# 1-sch.net
KiCad netlist of a schematic drawn in Altium Designer
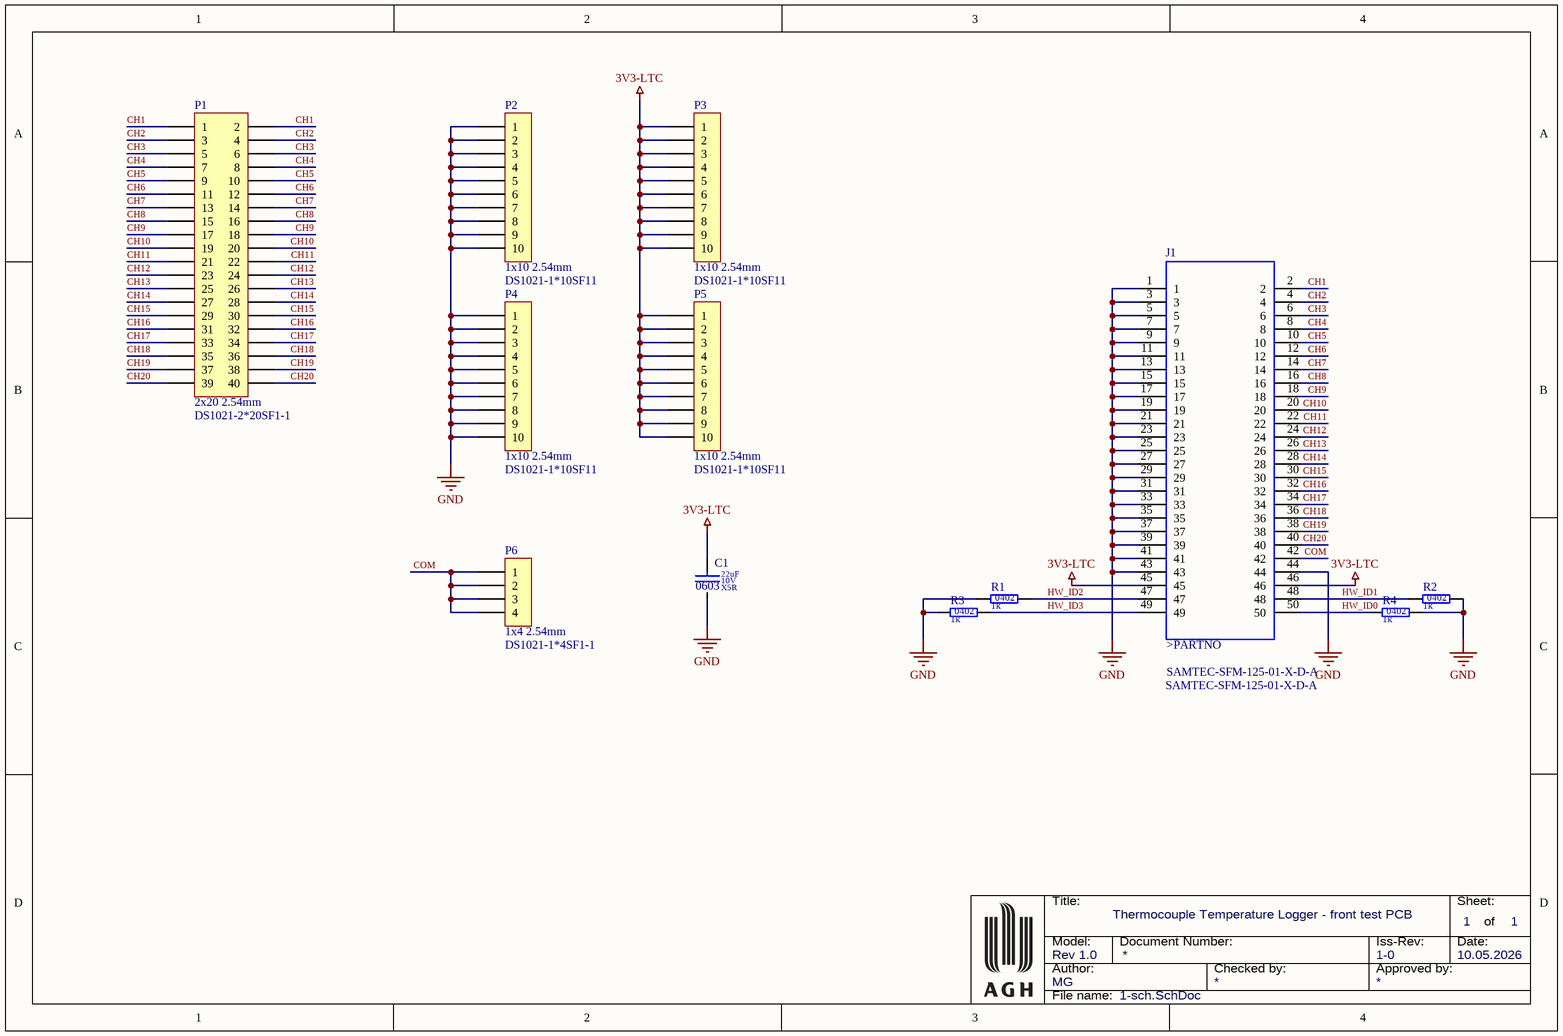
[diagram p0: 1-sch.SchDoc]

(export (version "E")
  (design (tool "Eeschema 10.0.6"))
  (components
    (comp (ref "C1")
      (value "22uF")
      (footprint "C_0603_1608")
      (description "Capacitor")
      (fields
        (field (name "DIELECTRIC") "X5R")
        (field (name "VOLTAGE") "10V")
        (field (name "SCH_FOOTPRINT") "0603")
        (field (name "PART NUMBER") "C_22uF_10V_X5R_0603_20")
        (field (name "MANUFACTURER") "Murata")
      )
      (libsource (lib "Library") (part "C"))
    )
    (comp (ref "J1")
      (value "SAMTEC-SFM-125-01-X-D-A")
      (footprint "SAMTEC-SFM-125-01-X-D-A")
      (libsource (lib "SAMTEC-SFM-125-01-X-D-A") (part "SAMTEC-SFM-125-01-X-D-A"))
    )
    (comp (ref "P1")
      (value "DS1021-2*20SF1-1")
      (footprint "P_HEADER_2x20_2.54")
      (description "Pin Header")
      (fields
        (field (name "SCH_FOOTPRINT") "2x20 2.54mm")
        (field (name "PART NUMBER") "P_HEADER_2x20_2.54")
        (field (name "MANUFACTURER") "Connfly")
      )
      (libsource (lib "Library") (part "P_HEADER_2x20"))
    )
    (comp (ref "P2")
      (value "DS1021-1*10SF11")
      (footprint "P_HEADER_1x10_2.54")
      (description "Pin Header")
      (fields
        (field (name "SCH_FOOTPRINT") "1x10 2.54mm")
        (field (name "PART NUMBER") "P_HEADER_1x10_2.54")
        (field (name "MANUFACTURER") "Connfly")
      )
      (libsource (lib "Library") (part "P_HEADER_1x10"))
    )
    (comp (ref "P3")
      (value "DS1021-1*10SF11")
      (footprint "P_HEADER_1x10_2.54")
      (description "Pin Header")
      (fields
        (field (name "SCH_FOOTPRINT") "1x10 2.54mm")
        (field (name "PART NUMBER") "P_HEADER_1x10_2.54")
        (field (name "MANUFACTURER") "Connfly")
      )
      (libsource (lib "Library") (part "P_HEADER_1x10"))
    )
    (comp (ref "P4")
      (value "DS1021-1*10SF11")
      (footprint "P_HEADER_1x10_2.54")
      (description "Pin Header")
      (fields
        (field (name "SCH_FOOTPRINT") "1x10 2.54mm")
        (field (name "PART NUMBER") "P_HEADER_1x10_2.54")
        (field (name "MANUFACTURER") "Connfly")
      )
      (libsource (lib "Library") (part "P_HEADER_1x10"))
    )
    (comp (ref "P5")
      (value "DS1021-1*10SF11")
      (footprint "P_HEADER_1x10_2.54")
      (description "Pin Header")
      (fields
        (field (name "SCH_FOOTPRINT") "1x10 2.54mm")
        (field (name "PART NUMBER") "P_HEADER_1x10_2.54")
        (field (name "MANUFACTURER") "Connfly")
      )
      (libsource (lib "Library") (part "P_HEADER_1x10"))
    )
    (comp (ref "P6")
      (value "DS1021-1*4SF1-1")
      (footprint "P_HEADER_1x4_2.54")
      (description "Pin Header")
      (fields
        (field (name "SCH_FOOTPRINT") "1x4 2.54mm")
        (field (name "PART NUMBER") "P_HEADER_1x4_2.54")
        (field (name "MANUFACTURER") "Connfly")
      )
      (libsource (lib "Library") (part "P_HEADER_1x4"))
    )
    (comp (ref "R1")
      (value "1k")
      (footprint "R_0402_1005")
      (fields
        (field (name "SCH_FOOTPRINT") "0402")
        (field (name "PART NUMBER") "R_1k_0402_1")
        (field (name "VOLTAGE") "50V")
        (field (name "POWER") "63mW")
      )
      (libsource (lib "Library") (part "R"))
    )
    (comp (ref "R2")
      (value "1k")
      (footprint "R_0402_1005")
      (fields
        (field (name "SCH_FOOTPRINT") "0402")
        (field (name "PART NUMBER") "R_1k_0402_1")
        (field (name "VOLTAGE") "50V")
        (field (name "POWER") "63mW")
      )
      (libsource (lib "Library") (part "R"))
    )
    (comp (ref "R3")
      (value "1k")
      (footprint "R_0402_1005")
      (fields
        (field (name "SCH_FOOTPRINT") "0402")
        (field (name "PART NUMBER") "R_1k_0402_1")
        (field (name "VOLTAGE") "50V")
        (field (name "POWER") "63mW")
      )
      (libsource (lib "Library") (part "R"))
    )
    (comp (ref "R4")
      (value "1k")
      (footprint "R_0402_1005")
      (fields
        (field (name "SCH_FOOTPRINT") "0402")
        (field (name "PART NUMBER") "R_1k_0402_1")
        (field (name "VOLTAGE") "50V")
        (field (name "POWER") "63mW")
      )
      (libsource (lib "Library") (part "R"))
    )
  )
  (nets
    (net (code "1") (name "/CH1") (class "Default")
      (node (ref "J1") (pin "2") (pinfunction "2_2") (pintype "passive"))
      (node (ref "P1") (pin "1") (pinfunction "1_1") (pintype "passive"))
      (node (ref "P1") (pin "2") (pinfunction "2_2") (pintype "passive"))
    )
    (net (code "2") (name "/CH2") (class "Default")
      (node (ref "J1") (pin "4") (pinfunction "4_4") (pintype "passive"))
      (node (ref "P1") (pin "3") (pinfunction "3_3") (pintype "passive"))
      (node (ref "P1") (pin "4") (pinfunction "4_4") (pintype "passive"))
    )
    (net (code "3") (name "/CH3") (class "Default")
      (node (ref "J1") (pin "6") (pinfunction "6_6") (pintype "passive"))
      (node (ref "P1") (pin "5") (pinfunction "5_5") (pintype "passive"))
      (node (ref "P1") (pin "6") (pinfunction "6_6") (pintype "passive"))
    )
    (net (code "4") (name "/CH4") (class "Default")
      (node (ref "J1") (pin "8") (pinfunction "8_8") (pintype "passive"))
      (node (ref "P1") (pin "7") (pinfunction "7_7") (pintype "passive"))
      (node (ref "P1") (pin "8") (pinfunction "8_8") (pintype "passive"))
    )
    (net (code "5") (name "/CH5") (class "Default")
      (node (ref "J1") (pin "10") (pinfunction "10_10") (pintype "passive"))
      (node (ref "P1") (pin "10") (pinfunction "10_10") (pintype "passive"))
      (node (ref "P1") (pin "9") (pinfunction "9_9") (pintype "passive"))
    )
    (net (code "6") (name "/CH6") (class "Default")
      (node (ref "J1") (pin "12") (pinfunction "12_12") (pintype "passive"))
      (node (ref "P1") (pin "11") (pinfunction "11_11") (pintype "passive"))
      (node (ref "P1") (pin "12") (pinfunction "12_12") (pintype "passive"))
    )
    (net (code "7") (name "/CH7") (class "Default")
      (node (ref "J1") (pin "14") (pinfunction "14_14") (pintype "passive"))
      (node (ref "P1") (pin "13") (pinfunction "13_13") (pintype "passive"))
      (node (ref "P1") (pin "14") (pinfunction "14_14") (pintype "passive"))
    )
    (net (code "8") (name "/CH8") (class "Default")
      (node (ref "J1") (pin "16") (pinfunction "16_16") (pintype "passive"))
      (node (ref "P1") (pin "15") (pinfunction "15_15") (pintype "passive"))
      (node (ref "P1") (pin "16") (pinfunction "16_16") (pintype "passive"))
    )
    (net (code "9") (name "/CH9") (class "Default")
      (node (ref "J1") (pin "18") (pinfunction "18_18") (pintype "passive"))
      (node (ref "P1") (pin "17") (pinfunction "17_17") (pintype "passive"))
      (node (ref "P1") (pin "18") (pinfunction "18_18") (pintype "passive"))
    )
    (net (code "10") (name "/CH10") (class "Default")
      (node (ref "J1") (pin "20") (pinfunction "20_20") (pintype "passive"))
      (node (ref "P1") (pin "19") (pinfunction "19_19") (pintype "passive"))
      (node (ref "P1") (pin "20") (pinfunction "20_20") (pintype "passive"))
    )
    (net (code "11") (name "/CH11") (class "Default")
      (node (ref "J1") (pin "22") (pinfunction "22_22") (pintype "passive"))
      (node (ref "P1") (pin "21") (pinfunction "21_21") (pintype "passive"))
      (node (ref "P1") (pin "22") (pinfunction "22_22") (pintype "passive"))
    )
    (net (code "12") (name "/CH12") (class "Default")
      (node (ref "J1") (pin "24") (pinfunction "24_24") (pintype "passive"))
      (node (ref "P1") (pin "23") (pinfunction "23_23") (pintype "passive"))
      (node (ref "P1") (pin "24") (pinfunction "24_24") (pintype "passive"))
    )
    (net (code "13") (name "/CH13") (class "Default")
      (node (ref "J1") (pin "26") (pinfunction "26_26") (pintype "passive"))
      (node (ref "P1") (pin "25") (pinfunction "25_25") (pintype "passive"))
      (node (ref "P1") (pin "26") (pinfunction "26_26") (pintype "passive"))
    )
    (net (code "14") (name "/CH14") (class "Default")
      (node (ref "J1") (pin "28") (pinfunction "28_28") (pintype "passive"))
      (node (ref "P1") (pin "27") (pinfunction "27_27") (pintype "passive"))
      (node (ref "P1") (pin "28") (pinfunction "28_28") (pintype "passive"))
    )
    (net (code "15") (name "/CH15") (class "Default")
      (node (ref "J1") (pin "30") (pinfunction "30_30") (pintype "passive"))
      (node (ref "P1") (pin "29") (pinfunction "29_29") (pintype "passive"))
      (node (ref "P1") (pin "30") (pinfunction "30_30") (pintype "passive"))
    )
    (net (code "16") (name "/CH16") (class "Default")
      (node (ref "J1") (pin "32") (pinfunction "32_32") (pintype "passive"))
      (node (ref "P1") (pin "31") (pinfunction "31_31") (pintype "passive"))
      (node (ref "P1") (pin "32") (pinfunction "32_32") (pintype "passive"))
    )
    (net (code "17") (name "/CH17") (class "Default")
      (node (ref "J1") (pin "34") (pinfunction "34_34") (pintype "passive"))
      (node (ref "P1") (pin "33") (pinfunction "33_33") (pintype "passive"))
      (node (ref "P1") (pin "34") (pinfunction "34_34") (pintype "passive"))
    )
    (net (code "18") (name "/CH18") (class "Default")
      (node (ref "J1") (pin "36") (pinfunction "36_36") (pintype "passive"))
      (node (ref "P1") (pin "35") (pinfunction "35_35") (pintype "passive"))
      (node (ref "P1") (pin "36") (pinfunction "36_36") (pintype "passive"))
    )
    (net (code "19") (name "/CH19") (class "Default")
      (node (ref "J1") (pin "38") (pinfunction "38_38") (pintype "passive"))
      (node (ref "P1") (pin "37") (pinfunction "37_37") (pintype "passive"))
      (node (ref "P1") (pin "38") (pinfunction "38_38") (pintype "passive"))
    )
    (net (code "20") (name "/CH20") (class "Default")
      (node (ref "J1") (pin "40") (pinfunction "40_40") (pintype "passive"))
      (node (ref "P1") (pin "39") (pinfunction "39_39") (pintype "passive"))
      (node (ref "P1") (pin "40") (pinfunction "40_40") (pintype "passive"))
    )
    (net (code "21") (name "/COM") (class "Default")
      (node (ref "J1") (pin "42") (pinfunction "42_42") (pintype "passive"))
      (node (ref "P6") (pin "1") (pinfunction "1_1") (pintype "passive"))
      (node (ref "P6") (pin "2") (pinfunction "2_2") (pintype "passive"))
      (node (ref "P6") (pin "3") (pinfunction "3_3") (pintype "passive"))
      (node (ref "P6") (pin "4") (pinfunction "4_4") (pintype "passive"))
    )
    (net (code "22") (name "/HW_ID0") (class "Default")
      (node (ref "J1") (pin "50") (pinfunction "50_50") (pintype "passive"))
      (node (ref "R4") (pin "1") (pinfunction "1_1") (pintype "passive"))
    )
    (net (code "23") (name "/HW_ID1") (class "Default")
      (node (ref "J1") (pin "48") (pinfunction "48_48") (pintype "passive"))
      (node (ref "R2") (pin "1") (pinfunction "1_1") (pintype "passive"))
    )
    (net (code "24") (name "/HW_ID2") (class "Default")
      (node (ref "J1") (pin "47") (pinfunction "47_47") (pintype "passive"))
      (node (ref "R1") (pin "2") (pinfunction "2_2") (pintype "passive"))
    )
    (net (code "25") (name "/HW_ID3") (class "Default")
      (node (ref "J1") (pin "49") (pinfunction "49_49") (pintype "passive"))
      (node (ref "R3") (pin "2") (pinfunction "2_2") (pintype "passive"))
    )
    (net (code "26") (name "3V3-LTC") (class "Default")
      (node (ref "C1") (pin "1") (pinfunction "1_1") (pintype "passive"))
      (node (ref "J1") (pin "45") (pinfunction "45_45") (pintype "passive"))
      (node (ref "J1") (pin "46") (pinfunction "46_46") (pintype "passive"))
      (node (ref "P3") (pin "1") (pinfunction "1_1") (pintype "passive"))
      (node (ref "P3") (pin "10") (pinfunction "10_10") (pintype "passive"))
      (node (ref "P3") (pin "2") (pinfunction "2_2") (pintype "passive"))
      (node (ref "P3") (pin "3") (pinfunction "3_3") (pintype "passive"))
      (node (ref "P3") (pin "4") (pinfunction "4_4") (pintype "passive"))
      (node (ref "P3") (pin "5") (pinfunction "5_5") (pintype "passive"))
      (node (ref "P3") (pin "6") (pinfunction "6_6") (pintype "passive"))
      (node (ref "P3") (pin "7") (pinfunction "7_7") (pintype "passive"))
      (node (ref "P3") (pin "8") (pinfunction "8_8") (pintype "passive"))
      (node (ref "P3") (pin "9") (pinfunction "9_9") (pintype "passive"))
      (node (ref "P5") (pin "1") (pinfunction "1_1") (pintype "passive"))
      (node (ref "P5") (pin "10") (pinfunction "10_10") (pintype "passive"))
      (node (ref "P5") (pin "2") (pinfunction "2_2") (pintype "passive"))
      (node (ref "P5") (pin "3") (pinfunction "3_3") (pintype "passive"))
      (node (ref "P5") (pin "4") (pinfunction "4_4") (pintype "passive"))
      (node (ref "P5") (pin "5") (pinfunction "5_5") (pintype "passive"))
      (node (ref "P5") (pin "6") (pinfunction "6_6") (pintype "passive"))
      (node (ref "P5") (pin "7") (pinfunction "7_7") (pintype "passive"))
      (node (ref "P5") (pin "8") (pinfunction "8_8") (pintype "passive"))
      (node (ref "P5") (pin "9") (pinfunction "9_9") (pintype "passive"))
    )
    (net (code "27") (name "GND") (class "Default")
      (node (ref "C1") (pin "2") (pinfunction "2_2") (pintype "passive"))
      (node (ref "J1") (pin "1") (pinfunction "1_1") (pintype "passive"))
      (node (ref "J1") (pin "11") (pinfunction "11_11") (pintype "passive"))
      (node (ref "J1") (pin "13") (pinfunction "13_13") (pintype "passive"))
      (node (ref "J1") (pin "15") (pinfunction "15_15") (pintype "passive"))
      (node (ref "J1") (pin "17") (pinfunction "17_17") (pintype "passive"))
      (node (ref "J1") (pin "19") (pinfunction "19_19") (pintype "passive"))
      (node (ref "J1") (pin "21") (pinfunction "21_21") (pintype "passive"))
      (node (ref "J1") (pin "23") (pinfunction "23_23") (pintype "passive"))
      (node (ref "J1") (pin "25") (pinfunction "25_25") (pintype "passive"))
      (node (ref "J1") (pin "27") (pinfunction "27_27") (pintype "passive"))
      (node (ref "J1") (pin "29") (pinfunction "29_29") (pintype "passive"))
      (node (ref "J1") (pin "3") (pinfunction "3_3") (pintype "passive"))
      (node (ref "J1") (pin "31") (pinfunction "31_31") (pintype "passive"))
      (node (ref "J1") (pin "33") (pinfunction "33_33") (pintype "passive"))
      (node (ref "J1") (pin "35") (pinfunction "35_35") (pintype "passive"))
      (node (ref "J1") (pin "37") (pinfunction "37_37") (pintype "passive"))
      (node (ref "J1") (pin "39") (pinfunction "39_39") (pintype "passive"))
      (node (ref "J1") (pin "41") (pinfunction "41_41") (pintype "passive"))
      (node (ref "J1") (pin "43") (pinfunction "43_43") (pintype "passive"))
      (node (ref "J1") (pin "44") (pinfunction "44_44") (pintype "passive"))
      (node (ref "J1") (pin "5") (pinfunction "5_5") (pintype "passive"))
      (node (ref "J1") (pin "7") (pinfunction "7_7") (pintype "passive"))
      (node (ref "J1") (pin "9") (pinfunction "9_9") (pintype "passive"))
      (node (ref "P2") (pin "1") (pinfunction "1_1") (pintype "passive"))
      (node (ref "P2") (pin "10") (pinfunction "10_10") (pintype "passive"))
      (node (ref "P2") (pin "2") (pinfunction "2_2") (pintype "passive"))
      (node (ref "P2") (pin "3") (pinfunction "3_3") (pintype "passive"))
      (node (ref "P2") (pin "4") (pinfunction "4_4") (pintype "passive"))
      (node (ref "P2") (pin "5") (pinfunction "5_5") (pintype "passive"))
      (node (ref "P2") (pin "6") (pinfunction "6_6") (pintype "passive"))
      (node (ref "P2") (pin "7") (pinfunction "7_7") (pintype "passive"))
      (node (ref "P2") (pin "8") (pinfunction "8_8") (pintype "passive"))
      (node (ref "P2") (pin "9") (pinfunction "9_9") (pintype "passive"))
      (node (ref "P4") (pin "1") (pinfunction "1_1") (pintype "passive"))
      (node (ref "P4") (pin "10") (pinfunction "10_10") (pintype "passive"))
      (node (ref "P4") (pin "2") (pinfunction "2_2") (pintype "passive"))
      (node (ref "P4") (pin "3") (pinfunction "3_3") (pintype "passive"))
      (node (ref "P4") (pin "4") (pinfunction "4_4") (pintype "passive"))
      (node (ref "P4") (pin "5") (pinfunction "5_5") (pintype "passive"))
      (node (ref "P4") (pin "6") (pinfunction "6_6") (pintype "passive"))
      (node (ref "P4") (pin "7") (pinfunction "7_7") (pintype "passive"))
      (node (ref "P4") (pin "8") (pinfunction "8_8") (pintype "passive"))
      (node (ref "P4") (pin "9") (pinfunction "9_9") (pintype "passive"))
      (node (ref "R1") (pin "1") (pinfunction "1_1") (pintype "passive"))
      (node (ref "R2") (pin "2") (pinfunction "2_2") (pintype "passive"))
      (node (ref "R3") (pin "1") (pinfunction "1_1") (pintype "passive"))
      (node (ref "R4") (pin "2") (pinfunction "2_2") (pintype "passive"))
    )
  )
)
